# led.net
KiCad netlist of a schematic drawn in EAGLE
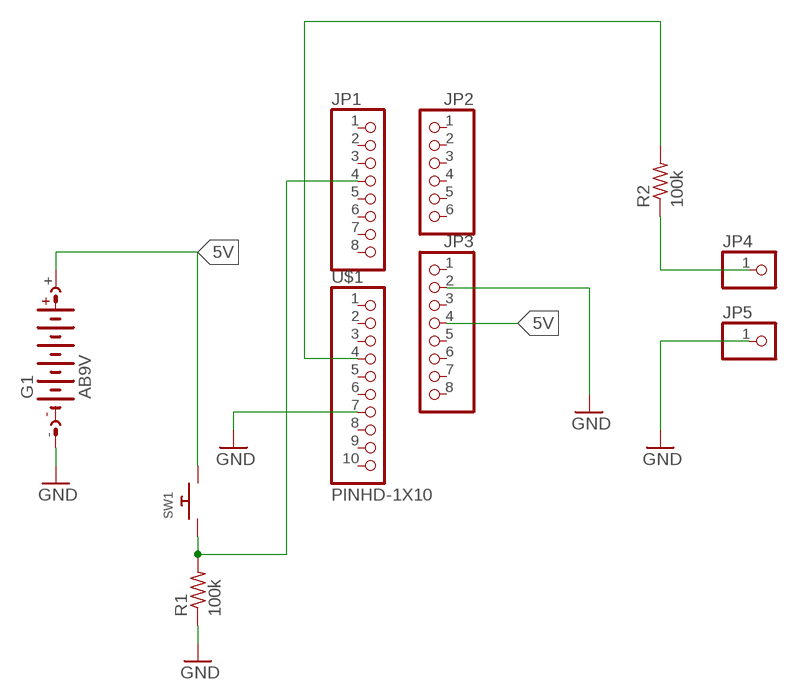
[diagram p0: schematic, sheet 1]

(export (version "E")
  (design (tool "Eeschema 10.0.6"))
  (components
    (comp (ref "G1")
      (value "AB9V")
      (footprint "eagle-import:AB9V")
      (libsource (lib "eagle-import") (part "AB9V"))
    )
    (comp (ref "JP1")
      (value "PINHD-1X8BIG")
      (footprint "eagle-import:1X08-BIG")
      (libsource (lib "eagle-import") (part "PINHD-1X8BIG"))
    )
    (comp (ref "JP2")
      (value "PINHD-1X6B")
      (footprint "eagle-import:1X06-BIG")
      (libsource (lib "eagle-import") (part "PINHD-1X6B"))
    )
    (comp (ref "JP3")
      (value "PINHD-1X8BIG")
      (footprint "eagle-import:1X08-BIG")
      (libsource (lib "eagle-import") (part "PINHD-1X8BIG"))
    )
    (comp (ref "JP4")
      (value "PINHD-1X1")
      (footprint "eagle-import:1X01")
      (libsource (lib "eagle-import") (part "PINHD-1X1"))
    )
    (comp (ref "JP5")
      (value "PINHD-1X1")
      (footprint "eagle-import:1X01")
      (libsource (lib "eagle-import") (part "PINHD-1X1"))
    )
    (comp (ref "R1")
      (value "100k")
      (footprint "eagle-import:0805-THM")
      (libsource (lib "eagle-import") (part "R-US_FLIPFLOP"))
    )
    (comp (ref "R2")
      (value "100k")
      (footprint "eagle-import:0805-THM")
      (libsource (lib "eagle-import") (part "R-US_FLIPFLOP"))
    )
    (comp (ref "SW1")
      (value "SWITCH_PUSHBUTTONSOFTTOUCHSMD_SJ")
      (footprint "eagle-import:PUSHBUTTON_SMD_SJ")
      (libsource (lib "eagle-import") (part "SWITCH_PUSHBUTTONSOFTTOUCHSMD_SJ"))
    )
    (comp (ref "U$1")
      (value "PINHD-1X10")
      (footprint "eagle-import:1X10-BIG")
      (libsource (lib "eagle-import") (part "PINHD-1X10"))
    )
  )
  (nets
    (net (code "1") (name "5V") (class "Default")
      (node (ref "G1") (pin "+") (pinfunction "+_+") (pintype "passive"))
      (node (ref "JP3") (pin "4") (pinfunction "4_4") (pintype "passive"))
      (node (ref "SW1") (pin "P$2") (pinfunction "P$2_P$2") (pintype "passive"))
    )
    (net (code "2") (name "GND") (class "Default")
      (node (ref "G1") (pin "-") (pinfunction "-_-") (pintype "passive"))
      (node (ref "JP3") (pin "2") (pinfunction "2_2") (pintype "passive"))
      (node (ref "JP5") (pin "1") (pinfunction "1_1") (pintype "passive"))
      (node (ref "R1") (pin "1") (pinfunction "1_1") (pintype "passive"))
      (node (ref "U$1") (pin "7") (pinfunction "7_7") (pintype "passive"))
    )
    (net (code "3") (name "Net-(JP1-Pad4)") (class "Default")
      (node (ref "JP1") (pin "4") (pinfunction "4_4") (pintype "passive"))
      (node (ref "R1") (pin "2") (pinfunction "2_2") (pintype "passive"))
      (node (ref "SW1") (pin "P$1") (pinfunction "P$1_P$1") (pintype "passive"))
    )
    (net (code "4") (name "Net-(JP4-Pad1)") (class "Default")
      (node (ref "JP4") (pin "1") (pinfunction "1_1") (pintype "passive"))
      (node (ref "R2") (pin "1") (pinfunction "1_1") (pintype "passive"))
    )
    (net (code "5") (name "Net-(R2-Pad2)") (class "Default")
      (node (ref "R2") (pin "2") (pinfunction "2_2") (pintype "passive"))
      (node (ref "U$1") (pin "4") (pinfunction "4_4") (pintype "passive"))
    )
    (net (code "6") (name "unconnected-(JP1-Pad1)") (class "Default")
      (node (ref "JP1") (pin "1") (pinfunction "1_1") (pintype "passive"))
    )
    (net (code "7") (name "unconnected-(JP1-Pad2)") (class "Default")
      (node (ref "JP1") (pin "2") (pinfunction "2_2") (pintype "passive"))
    )
    (net (code "8") (name "unconnected-(JP1-Pad3)") (class "Default")
      (node (ref "JP1") (pin "3") (pinfunction "3_3") (pintype "passive"))
    )
    (net (code "9") (name "unconnected-(JP1-Pad5)") (class "Default")
      (node (ref "JP1") (pin "5") (pinfunction "5_5") (pintype "passive"))
    )
    (net (code "10") (name "unconnected-(JP1-Pad6)") (class "Default")
      (node (ref "JP1") (pin "6") (pinfunction "6_6") (pintype "passive"))
    )
    (net (code "11") (name "unconnected-(JP1-Pad7)") (class "Default")
      (node (ref "JP1") (pin "7") (pinfunction "7_7") (pintype "passive"))
    )
    (net (code "12") (name "unconnected-(JP1-Pad8)") (class "Default")
      (node (ref "JP1") (pin "8") (pinfunction "8_8") (pintype "passive"))
    )
    (net (code "13") (name "unconnected-(JP2-Pad1)") (class "Default")
      (node (ref "JP2") (pin "1") (pinfunction "1_1") (pintype "passive"))
    )
    (net (code "14") (name "unconnected-(JP2-Pad2)") (class "Default")
      (node (ref "JP2") (pin "2") (pinfunction "2_2") (pintype "passive"))
    )
    (net (code "15") (name "unconnected-(JP2-Pad3)") (class "Default")
      (node (ref "JP2") (pin "3") (pinfunction "3_3") (pintype "passive"))
    )
    (net (code "16") (name "unconnected-(JP2-Pad4)") (class "Default")
      (node (ref "JP2") (pin "4") (pinfunction "4_4") (pintype "passive"))
    )
    (net (code "17") (name "unconnected-(JP2-Pad5)") (class "Default")
      (node (ref "JP2") (pin "5") (pinfunction "5_5") (pintype "passive"))
    )
    (net (code "18") (name "unconnected-(JP2-Pad6)") (class "Default")
      (node (ref "JP2") (pin "6") (pinfunction "6_6") (pintype "passive"))
    )
    (net (code "19") (name "unconnected-(JP3-Pad1)") (class "Default")
      (node (ref "JP3") (pin "1") (pinfunction "1_1") (pintype "passive"))
    )
    (net (code "20") (name "unconnected-(JP3-Pad3)") (class "Default")
      (node (ref "JP3") (pin "3") (pinfunction "3_3") (pintype "passive"))
    )
    (net (code "21") (name "unconnected-(JP3-Pad5)") (class "Default")
      (node (ref "JP3") (pin "5") (pinfunction "5_5") (pintype "passive"))
    )
    (net (code "22") (name "unconnected-(JP3-Pad6)") (class "Default")
      (node (ref "JP3") (pin "6") (pinfunction "6_6") (pintype "passive"))
    )
    (net (code "23") (name "unconnected-(JP3-Pad7)") (class "Default")
      (node (ref "JP3") (pin "7") (pinfunction "7_7") (pintype "passive"))
    )
    (net (code "24") (name "unconnected-(JP3-Pad8)") (class "Default")
      (node (ref "JP3") (pin "8") (pinfunction "8_8") (pintype "passive"))
    )
    (net (code "25") (name "unconnected-(U$1-Pad1)") (class "Default")
      (node (ref "U$1") (pin "1") (pinfunction "1_1") (pintype "passive"))
    )
    (net (code "26") (name "unconnected-(U$1-Pad2)") (class "Default")
      (node (ref "U$1") (pin "2") (pinfunction "2_2") (pintype "passive"))
    )
    (net (code "27") (name "unconnected-(U$1-Pad3)") (class "Default")
      (node (ref "U$1") (pin "3") (pinfunction "3_3") (pintype "passive"))
    )
    (net (code "28") (name "unconnected-(U$1-Pad5)") (class "Default")
      (node (ref "U$1") (pin "5") (pinfunction "5_5") (pintype "passive"))
    )
    (net (code "29") (name "unconnected-(U$1-Pad6)") (class "Default")
      (node (ref "U$1") (pin "6") (pinfunction "6_6") (pintype "passive"))
    )
    (net (code "30") (name "unconnected-(U$1-Pad8)") (class "Default")
      (node (ref "U$1") (pin "8") (pinfunction "8_8") (pintype "passive"))
    )
    (net (code "31") (name "unconnected-(U$1-Pad9)") (class "Default")
      (node (ref "U$1") (pin "9") (pinfunction "9_9") (pintype "passive"))
    )
    (net (code "32") (name "unconnected-(U$1-Pad10)") (class "Default")
      (node (ref "U$1") (pin "10") (pinfunction "10_10") (pintype "passive"))
    )
  )
)
